# Analog.net
KiCad netlist of a schematic drawn in Altium Designer
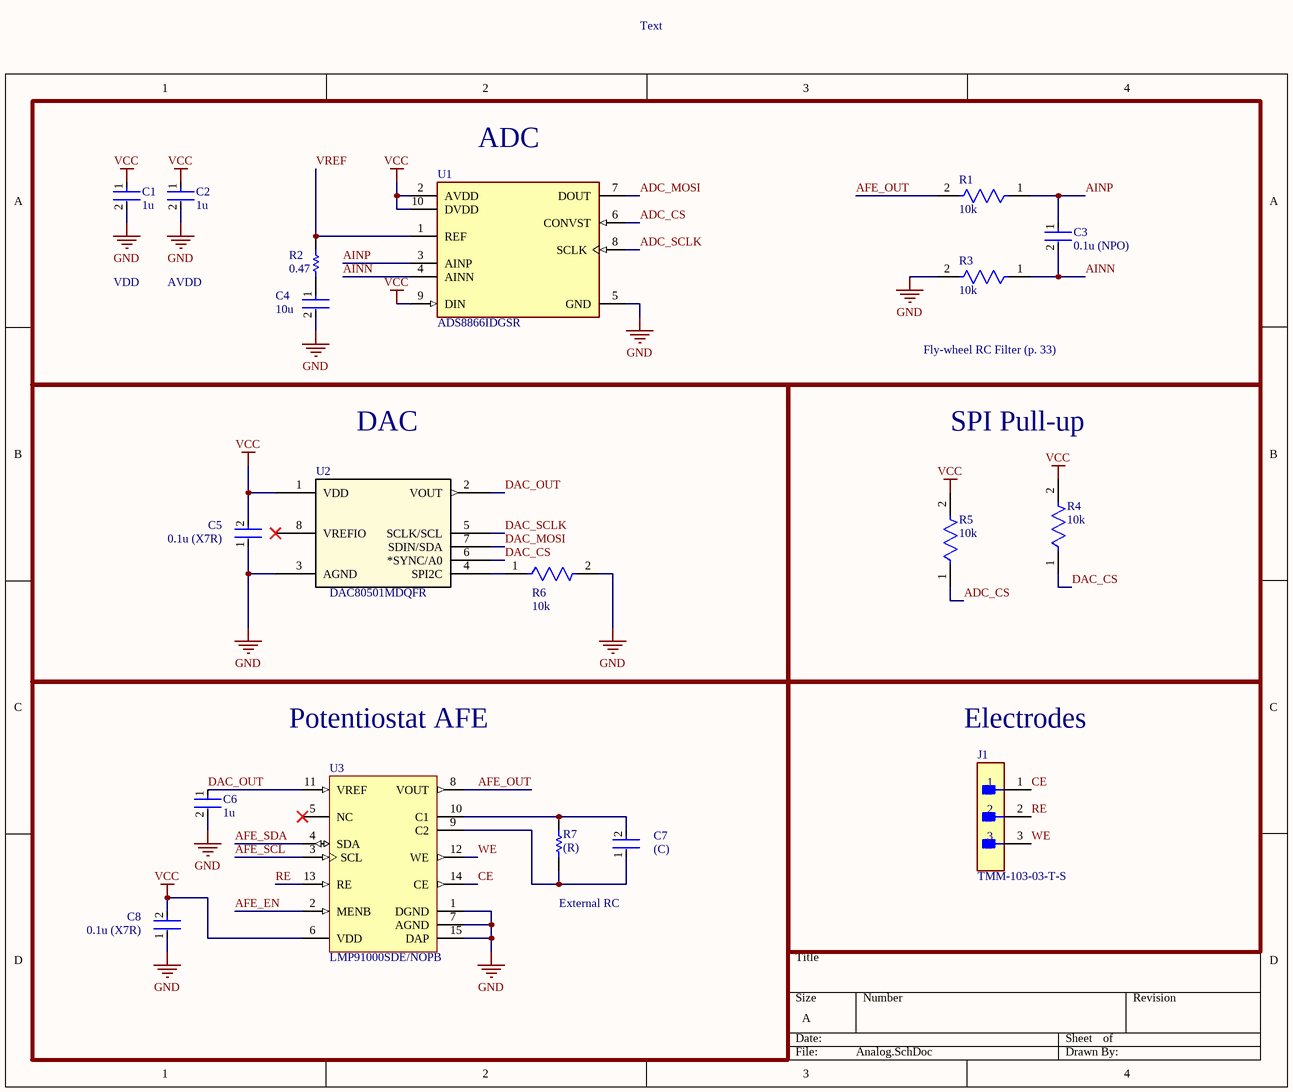
[diagram p0: Analog.SchDoc]

(export (version "E")
  (design (tool "Eeschema 10.0.6"))
  (components
    (comp (ref "C1")
      (value "1u")
      (footprint "FP-GCM188-0_1-IPC_B")
      (description "Ceramic Capacitor for Automotive 1uF  ±10% 16VDC X7R 0603 Paper T/R")
      (fields (field (name "VOLTAGE") "16V") (field (name "TOLERANCE") "10%"))
      (libsource (lib "Altium Content Vault") (part "02cd4be3c70576c341d710602a673aa"))
    )
    (comp (ref "C2")
      (value "1u")
      (footprint "FP-GCM188-0_1-IPC_B")
      (description "Ceramic Capacitor for Automotive 1uF  ±10% 16VDC X7R 0603 Paper T/R")
      (fields (field (name "VOLTAGE") "16V") (field (name "TOLERANCE") "10%"))
      (libsource (lib "Altium Content Vault") (part "02cd4be3c70576c341d710602a673aa"))
    )
    (comp (ref "C3")
      (value "0.1u (NPO)")
      (footprint "FP-GRM319-0_15-MFG")
      (description "Chip Multilayer Ceramic Capacitors for General Purpose, 1206, 0.10uF, C0G, 30ppm/°C, 5%, 50V")
      (libsource (lib "Altium Content Vault") (part "b4654b650e69147ec39a6b967a45e02"))
    )
    (comp (ref "C4")
      (value "10u")
      (footprint "FP-GRM21B-0_15-MFG")
      (description "Chip Multilayer Ceramic Capacitors for General Purpose, 0805, 10uF, X7R, 15%, 10%, 10V")
      (fields (field (name "TOLERANCE") "10%"))
      (libsource (lib "Altium Content Vault") (part "b4654b650e69147ec39a6b967a45e02"))
    )
    (comp (ref "C5")
      (value "0.1u (X7R)")
      (footprint "FP-GCJ188-0_2-IPC_C")
      (description "Cap Ceramic 0.1uF 50V X7R 10% Pad SMD 0603 Soft Termination +125°C Automotive T/R")
      (fields (field (name "TOLERANCE") "10%"))
      (libsource (lib "Altium Content Vault") (part "f23184f103b6ebe33a8c269c53dcba6"))
    )
    (comp (ref "C6")
      (value "1u")
      (footprint "FP-GCM188-0_1-IPC_B")
      (description "Ceramic Capacitor for Automotive 1uF  ±10% 16VDC X7R 0603 Paper T/R")
      (fields (field (name "VOLTAGE") "16V") (field (name "TOLERANCE") "10%"))
      (libsource (lib "Altium Content Vault") (part "02cd4be3c70576c341d710602a673aa"))
    )
    (comp (ref "C7")
      (value "(C)")
      (footprint "FP-GCJ188-0_2-IPC_C")
      (description "Cap Ceramic 0.1uF 50V X7R 10% Pad SMD 0603 Soft Termination +125°C Automotive T/R")
      (fields (field (name "TOLERANCE") "10%"))
      (libsource (lib "Altium Content Vault") (part "f23184f103b6ebe33a8c269c53dcba6"))
    )
    (comp (ref "C8")
      (value "0.1u (X7R)")
      (footprint "FP-GCJ188-0_2-IPC_C")
      (description "Cap Ceramic 0.1uF 50V X7R 10% Pad SMD 0603 Soft Termination +125°C Automotive T/R")
      (fields (field (name "TOLERANCE") "10%"))
      (libsource (lib "Altium Content Vault") (part "f23184f103b6ebe33a8c269c53dcba6"))
    )
    (comp (ref "J1")
      (value "TMM-103-03-T-S")
      (footprint "FP-TMM-103-03-T-S-MFG")
      (description "CONN HEADER VERT 3POS 2MM")
      (libsource (lib "Altium Content Vault") (part "0d3f023dd272f625e17a2be33dea85f"))
    )
    (comp (ref "R1")
      (value "10k")
      (footprint "FP-CPF0603-MFG")
      (description "RES SMD 10KΩ 1% 1/16W 0603")
      (fields (field (name "MANUFACTURER PART NUMBER") "CPF0603F10KC1") (field (name "TOLERANCE") "1%"))
      (libsource (lib "Altium Content Vault") (part "1029c3af85768c4190bb7ad29bc67b5"))
    )
    (comp (ref "R2")
      (value "0.47")
      (footprint "RESC1608X55X30ML15T15")
      (fields (field (name "MANUFACTURER") "Panasonic") (field (name "PART NUMBER") "ERJ-3RQFR47V"))
      (libsource (lib "Altium Content Vault") (part "RES"))
    )
    (comp (ref "R3")
      (value "10k")
      (footprint "FP-CPF0603-MFG")
      (description "RES SMD 10KΩ 1% 1/16W 0603")
      (fields (field (name "MANUFACTURER PART NUMBER") "CPF0603F10KC1") (field (name "TOLERANCE") "1%"))
      (libsource (lib "Altium Content Vault") (part "1029c3af85768c4190bb7ad29bc67b5"))
    )
    (comp (ref "R4")
      (value "10k")
      (footprint "FP-CPF0603-MFG")
      (description "RES SMD 10KΩ 1% 1/16W 0603")
      (fields (field (name "MANUFACTURER PART NUMBER") "CPF0603F10KC1") (field (name "TOLERANCE") "1%"))
      (libsource (lib "Altium Content Vault") (part "1029c3af85768c4190bb7ad29bc67b5"))
    )
    (comp (ref "R5")
      (value "10k")
      (footprint "FP-CPF0603-MFG")
      (description "RES SMD 10KΩ 1% 1/16W 0603")
      (fields (field (name "MANUFACTURER PART NUMBER") "CPF0603F10KC1") (field (name "TOLERANCE") "1%"))
      (libsource (lib "Altium Content Vault") (part "1029c3af85768c4190bb7ad29bc67b5"))
    )
    (comp (ref "R6")
      (value "10k")
      (footprint "FP-CPF0603-MFG")
      (description "RES SMD 10KΩ 1% 1/16W 0603")
      (fields (field (name "MANUFACTURER PART NUMBER") "CPF0603F10KC1") (field (name "TOLERANCE") "1%"))
      (libsource (lib "Altium Content Vault") (part "1029c3af85768c4190bb7ad29bc67b5"))
    )
    (comp (ref "R7")
      (value "(R)")
      (footprint "RESC1005X40X25NL05T10")
      (fields (field (name "MANUFACTURER") "Yageo / Phycomp") (field (name "PART NUMBER") "RC0402FR-073M3L"))
      (libsource (lib "Altium Content Vault") (part "RES"))
    )
    (comp (ref "U1")
      (value "ADS8866IDGSR")
      (footprint "FP-DGS0010A-IPC_A")
      (description "IC ADC 16BIT SAR 10VSSOP")
      (libsource (lib "Altium Content Vault") (part "0bba3fc7ad278d053e037645b2d5400"))
    )
    (comp (ref "U2")
      (value "DAC80501MDQFR")
      (footprint "WSON8_2P1X2P1_TEX")
      (description "True 16-bit, 1-ch, SPI/I2C, voltage-output DAC in WSON package with precision internal reference")
      (libsource (lib "DAC80501MDQFR") (part "DAC80501MDQFR"))
    )
    (comp (ref "U3")
      (value "LMP91000SDE/NOPB")
      (footprint "NHL0014B_V")
      (description "Configurable AFE Potentiostat for Low-Power Chemical Sensing Applications, 14-pin LLP, 250 Reel")
      (fields (field (name "MANUFACTURER") "Texas Instruments"))
      (libsource (lib "Altium Content Vault") (part "SEN-ELECHEM-LMP91000-15"))
    )
  )
  (nets
    (net (code "1") (name "/ADC_CS") (class "Default")
      (node (ref "R5") (pin "1") (pinfunction "1_1") (pintype "passive"))
      (node (ref "U1") (pin "6") (pinfunction "CONVST_6") (pintype "input"))
    )
    (net (code "2") (name "/ADC_MOSI") (class "Default")
      (node (ref "U1") (pin "7") (pinfunction "DOUT_7") (pintype "passive"))
    )
    (net (code "3") (name "/ADC_SCLK") (class "Default")
      (node (ref "U1") (pin "8") (pinfunction "SCLK_8") (pintype "input"))
    )
    (net (code "4") (name "/AFE_EN") (class "Default")
      (node (ref "U3") (pin "2") (pinfunction "MENB_2") (pintype "input"))
    )
    (net (code "5") (name "/AFE_OUT") (class "Default")
      (node (ref "R1") (pin "2") (pinfunction "2_2") (pintype "passive"))
      (node (ref "U3") (pin "8") (pinfunction "VOUT_8") (pintype "output"))
    )
    (net (code "6") (name "/AFE_SCL") (class "Default")
      (node (ref "U3") (pin "3") (pinfunction "SCL_3") (pintype "input"))
    )
    (net (code "7") (name "/AFE_SDA") (class "Default")
      (node (ref "U3") (pin "4") (pinfunction "SDA_4") (pintype "bidirectional"))
    )
    (net (code "8") (name "/AINN") (class "Default")
      (node (ref "C3") (pin "2") (pinfunction "2_2") (pintype "passive"))
      (node (ref "R3") (pin "1") (pinfunction "1_1") (pintype "passive"))
      (node (ref "U1") (pin "4") (pinfunction "AINN_4") (pintype "passive"))
    )
    (net (code "9") (name "/AINP") (class "Default")
      (node (ref "C3") (pin "1") (pinfunction "1_1") (pintype "passive"))
      (node (ref "R1") (pin "1") (pinfunction "1_1") (pintype "passive"))
      (node (ref "U1") (pin "3") (pinfunction "AINP_3") (pintype "passive"))
    )
    (net (code "10") (name "/CE") (class "Default")
      (node (ref "J1") (pin "1") (pinfunction "1_1") (pintype "passive"))
      (node (ref "U3") (pin "14") (pinfunction "CE_14") (pintype "output"))
    )
    (net (code "11") (name "/DAC_CS") (class "Default")
      (node (ref "R4") (pin "1") (pinfunction "1_1") (pintype "passive"))
      (node (ref "U2") (pin "6") (pinfunction "*SYNC/A0_6") (pintype "passive"))
    )
    (net (code "12") (name "/DAC_MOSI") (class "Default")
      (node (ref "U2") (pin "7") (pinfunction "SDIN/SDA_7") (pintype "passive"))
    )
    (net (code "13") (name "/DAC_OUT") (class "Default")
      (node (ref "C6") (pin "1") (pinfunction "1_1") (pintype "passive"))
      (node (ref "U2") (pin "2") (pinfunction "VOUT_2") (pintype "output"))
      (node (ref "U3") (pin "11") (pinfunction "VREF_11") (pintype "input"))
    )
    (net (code "14") (name "/DAC_SCLK") (class "Default")
      (node (ref "U2") (pin "5") (pinfunction "SCLK/SCL_5") (pintype "passive"))
    )
    (net (code "15") (name "/RE") (class "Default")
      (node (ref "J1") (pin "2") (pinfunction "2_2") (pintype "passive"))
      (node (ref "U3") (pin "13") (pinfunction "RE_13") (pintype "input"))
    )
    (net (code "16") (name "/VREF") (class "Default")
      (node (ref "R2") (pin "2") (pinfunction "2_2") (pintype "passive"))
      (node (ref "U1") (pin "1") (pinfunction "REF_1") (pintype "passive"))
    )
    (net (code "17") (name "/WE") (class "Default")
      (node (ref "J1") (pin "3") (pinfunction "3_3") (pintype "passive"))
      (node (ref "U3") (pin "12") (pinfunction "WE_12") (pintype "output"))
    )
    (net (code "18") (name "GND") (class "Default")
      (node (ref "C1") (pin "2") (pinfunction "2_2") (pintype "passive"))
      (node (ref "C2") (pin "2") (pinfunction "2_2") (pintype "passive"))
      (node (ref "C4") (pin "2") (pinfunction "2_2") (pintype "passive"))
      (node (ref "C5") (pin "1") (pinfunction "1_1") (pintype "passive"))
      (node (ref "C6") (pin "2") (pinfunction "2_2") (pintype "passive"))
      (node (ref "C8") (pin "1") (pinfunction "1_1") (pintype "passive"))
      (node (ref "R3") (pin "2") (pinfunction "2_2") (pintype "passive"))
      (node (ref "R6") (pin "2") (pinfunction "2_2") (pintype "passive"))
      (node (ref "U1") (pin "5") (pinfunction "GND_5") (pintype "power_in"))
      (node (ref "U2") (pin "3") (pinfunction "AGND_3") (pintype "power_in"))
      (node (ref "U3") (pin "1") (pinfunction "DGND_1") (pintype "power_in"))
      (node (ref "U3") (pin "15") (pinfunction "DAP_15") (pintype "power_in"))
      (node (ref "U3") (pin "7") (pinfunction "AGND_7") (pintype "power_in"))
    )
    (net (code "19") (name "Net-(C4-Pad1)") (class "Default")
      (node (ref "C4") (pin "1") (pinfunction "1_1") (pintype "passive"))
      (node (ref "R2") (pin "1") (pinfunction "1_1") (pintype "passive"))
    )
    (net (code "20") (name "Net-(U2-SPI2C)") (class "Default")
      (node (ref "R6") (pin "1") (pinfunction "1_1") (pintype "passive"))
      (node (ref "U2") (pin "4") (pinfunction "SPI2C_4") (pintype "passive"))
    )
    (net (code "21") (name "Net-(U3-C1)") (class "Default")
      (node (ref "C7") (pin "2") (pinfunction "2_2") (pintype "passive"))
      (node (ref "R7") (pin "2") (pinfunction "2_2") (pintype "passive"))
      (node (ref "U3") (pin "10") (pinfunction "C1_10") (pintype "passive"))
    )
    (net (code "22") (name "Net-(U3-C2)") (class "Default")
      (node (ref "C7") (pin "1") (pinfunction "1_1") (pintype "passive"))
      (node (ref "R7") (pin "1") (pinfunction "1_1") (pintype "passive"))
      (node (ref "U3") (pin "9") (pinfunction "C2_9") (pintype "passive"))
    )
    (net (code "23") (name "VCC") (class "Default")
      (node (ref "C1") (pin "1") (pinfunction "1_1") (pintype "passive"))
      (node (ref "C2") (pin "1") (pinfunction "1_1") (pintype "passive"))
      (node (ref "C5") (pin "2") (pinfunction "2_2") (pintype "passive"))
      (node (ref "C8") (pin "2") (pinfunction "2_2") (pintype "passive"))
      (node (ref "R4") (pin "2") (pinfunction "2_2") (pintype "passive"))
      (node (ref "R5") (pin "2") (pinfunction "2_2") (pintype "passive"))
      (node (ref "U1") (pin "10") (pinfunction "DVDD_10") (pintype "power_in"))
      (node (ref "U1") (pin "2") (pinfunction "AVDD_2") (pintype "power_in"))
      (node (ref "U1") (pin "9") (pinfunction "DIN_9") (pintype "input"))
      (node (ref "U2") (pin "1") (pinfunction "VDD_1") (pintype "power_in"))
      (node (ref "U3") (pin "6") (pinfunction "VDD_6") (pintype "power_in"))
    )
    (net (code "24") (name "unconnected-(U2-VREFIO-Pad8)") (class "Default")
      (node (ref "U2") (pin "8") (pinfunction "VREFIO_8") (pintype "power_in+no_connect"))
    )
    (net (code "25") (name "unconnected-(U3-NC-Pad5)") (class "Default")
      (node (ref "U3") (pin "5") (pinfunction "NC_5") (pintype "passive+no_connect"))
    )
  )
)
